# GPR_ADAPTER.net
KiCad netlist of a schematic drawn in EAGLE
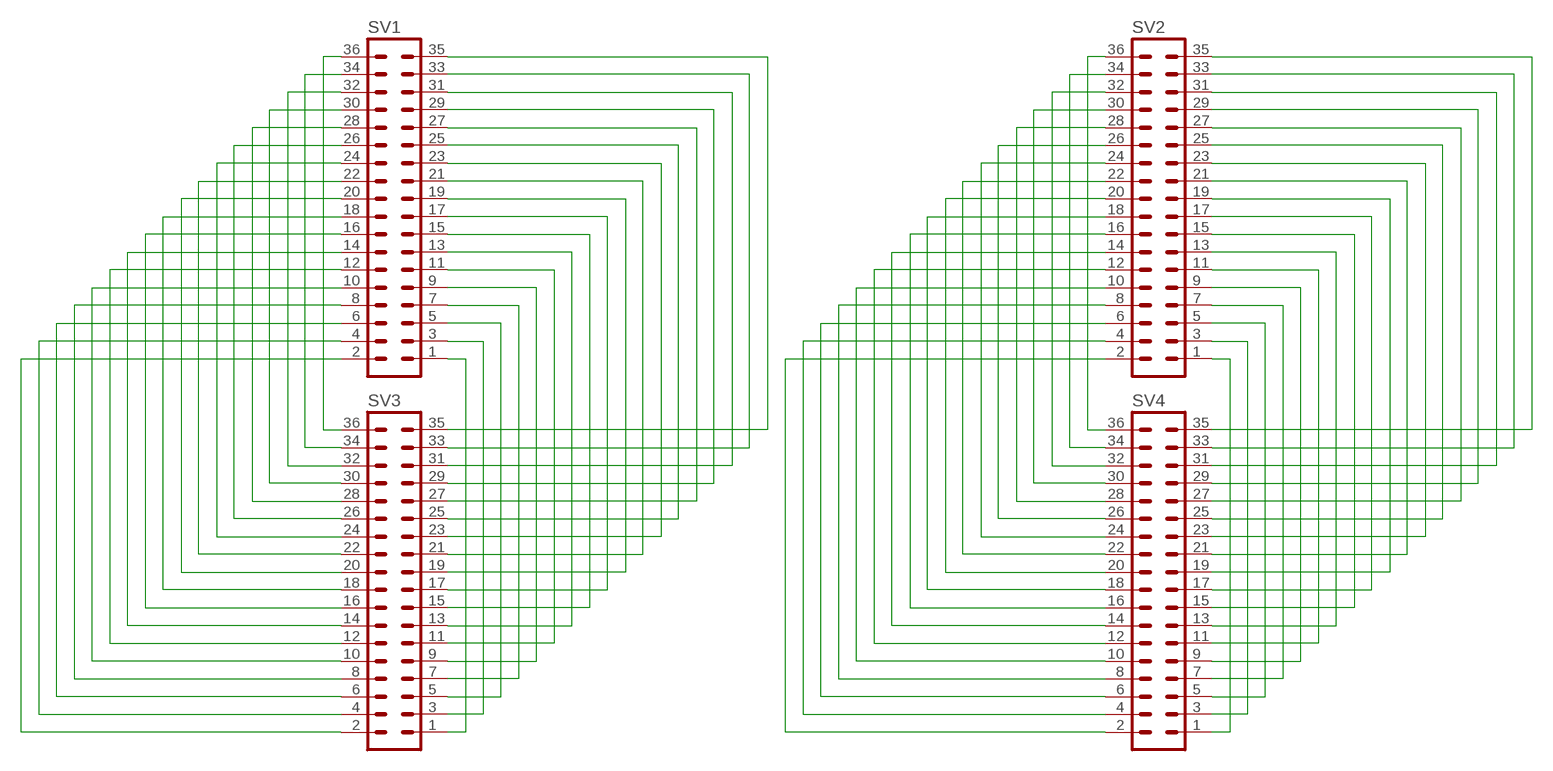
[diagram p0: schematic, sheet 1]

(export (version "E")
  (design (tool "Eeschema 10.0.6"))
  (components
    (comp (ref "SV1")
      (value "MA18-2")
      (footprint "eagle-import:MA18-2")
      (libsource (lib "eagle-import") (part "MA18-2"))
    )
    (comp (ref "SV2")
      (value "MA18-2")
      (footprint "eagle-import:MA18-2")
      (libsource (lib "eagle-import") (part "MA18-2"))
    )
    (comp (ref "SV3")
      (value "MA18-2")
      (footprint "eagle-import:MA18-2")
      (libsource (lib "eagle-import") (part "MA18-2"))
    )
    (comp (ref "SV4")
      (value "MA18-2")
      (footprint "eagle-import:MA18-2")
      (libsource (lib "eagle-import") (part "MA18-2"))
    )
  )
  (nets
    (net (code "1") (name "Net-(SV1-Pad1)") (class "Default")
      (node (ref "SV1") (pin "1") (pinfunction "1_1") (pintype "passive"))
      (node (ref "SV3") (pin "1") (pinfunction "1_1") (pintype "passive"))
    )
    (net (code "2") (name "Net-(SV1-Pad2)") (class "Default")
      (node (ref "SV1") (pin "2") (pinfunction "2_2") (pintype "passive"))
      (node (ref "SV3") (pin "2") (pinfunction "2_2") (pintype "passive"))
    )
    (net (code "3") (name "Net-(SV1-Pad3)") (class "Default")
      (node (ref "SV1") (pin "3") (pinfunction "3_3") (pintype "passive"))
      (node (ref "SV3") (pin "3") (pinfunction "3_3") (pintype "passive"))
    )
    (net (code "4") (name "Net-(SV1-Pad4)") (class "Default")
      (node (ref "SV1") (pin "4") (pinfunction "4_4") (pintype "passive"))
      (node (ref "SV3") (pin "4") (pinfunction "4_4") (pintype "passive"))
    )
    (net (code "5") (name "Net-(SV1-Pad5)") (class "Default")
      (node (ref "SV1") (pin "5") (pinfunction "5_5") (pintype "passive"))
      (node (ref "SV3") (pin "5") (pinfunction "5_5") (pintype "passive"))
    )
    (net (code "6") (name "Net-(SV1-Pad6)") (class "Default")
      (node (ref "SV1") (pin "6") (pinfunction "6_6") (pintype "passive"))
      (node (ref "SV3") (pin "6") (pinfunction "6_6") (pintype "passive"))
    )
    (net (code "7") (name "Net-(SV1-Pad7)") (class "Default")
      (node (ref "SV1") (pin "7") (pinfunction "7_7") (pintype "passive"))
      (node (ref "SV3") (pin "7") (pinfunction "7_7") (pintype "passive"))
    )
    (net (code "8") (name "Net-(SV1-Pad8)") (class "Default")
      (node (ref "SV1") (pin "8") (pinfunction "8_8") (pintype "passive"))
      (node (ref "SV3") (pin "8") (pinfunction "8_8") (pintype "passive"))
    )
    (net (code "9") (name "Net-(SV1-Pad9)") (class "Default")
      (node (ref "SV1") (pin "9") (pinfunction "9_9") (pintype "passive"))
      (node (ref "SV3") (pin "9") (pinfunction "9_9") (pintype "passive"))
    )
    (net (code "10") (name "Net-(SV1-Pad10)") (class "Default")
      (node (ref "SV1") (pin "10") (pinfunction "10_10") (pintype "passive"))
      (node (ref "SV3") (pin "10") (pinfunction "10_10") (pintype "passive"))
    )
    (net (code "11") (name "Net-(SV1-Pad11)") (class "Default")
      (node (ref "SV1") (pin "11") (pinfunction "11_11") (pintype "passive"))
      (node (ref "SV3") (pin "11") (pinfunction "11_11") (pintype "passive"))
    )
    (net (code "12") (name "Net-(SV1-Pad12)") (class "Default")
      (node (ref "SV1") (pin "12") (pinfunction "12_12") (pintype "passive"))
      (node (ref "SV3") (pin "12") (pinfunction "12_12") (pintype "passive"))
    )
    (net (code "13") (name "Net-(SV1-Pad13)") (class "Default")
      (node (ref "SV1") (pin "13") (pinfunction "13_13") (pintype "passive"))
      (node (ref "SV3") (pin "13") (pinfunction "13_13") (pintype "passive"))
    )
    (net (code "14") (name "Net-(SV1-Pad14)") (class "Default")
      (node (ref "SV1") (pin "14") (pinfunction "14_14") (pintype "passive"))
      (node (ref "SV3") (pin "14") (pinfunction "14_14") (pintype "passive"))
    )
    (net (code "15") (name "Net-(SV1-Pad15)") (class "Default")
      (node (ref "SV1") (pin "15") (pinfunction "15_15") (pintype "passive"))
      (node (ref "SV3") (pin "15") (pinfunction "15_15") (pintype "passive"))
    )
    (net (code "16") (name "Net-(SV1-Pad16)") (class "Default")
      (node (ref "SV1") (pin "16") (pinfunction "16_16") (pintype "passive"))
      (node (ref "SV3") (pin "16") (pinfunction "16_16") (pintype "passive"))
    )
    (net (code "17") (name "Net-(SV1-Pad17)") (class "Default")
      (node (ref "SV1") (pin "17") (pinfunction "17_17") (pintype "passive"))
      (node (ref "SV3") (pin "17") (pinfunction "17_17") (pintype "passive"))
    )
    (net (code "18") (name "Net-(SV1-Pad18)") (class "Default")
      (node (ref "SV1") (pin "18") (pinfunction "18_18") (pintype "passive"))
      (node (ref "SV3") (pin "18") (pinfunction "18_18") (pintype "passive"))
    )
    (net (code "19") (name "Net-(SV1-Pad19)") (class "Default")
      (node (ref "SV1") (pin "19") (pinfunction "19_19") (pintype "passive"))
      (node (ref "SV3") (pin "19") (pinfunction "19_19") (pintype "passive"))
    )
    (net (code "20") (name "Net-(SV1-Pad20)") (class "Default")
      (node (ref "SV1") (pin "20") (pinfunction "20_20") (pintype "passive"))
      (node (ref "SV3") (pin "20") (pinfunction "20_20") (pintype "passive"))
    )
    (net (code "21") (name "Net-(SV1-Pad21)") (class "Default")
      (node (ref "SV1") (pin "21") (pinfunction "21_21") (pintype "passive"))
      (node (ref "SV3") (pin "21") (pinfunction "21_21") (pintype "passive"))
    )
    (net (code "22") (name "Net-(SV1-Pad22)") (class "Default")
      (node (ref "SV1") (pin "22") (pinfunction "22_22") (pintype "passive"))
      (node (ref "SV3") (pin "22") (pinfunction "22_22") (pintype "passive"))
    )
    (net (code "23") (name "Net-(SV1-Pad23)") (class "Default")
      (node (ref "SV1") (pin "23") (pinfunction "23_23") (pintype "passive"))
      (node (ref "SV3") (pin "23") (pinfunction "23_23") (pintype "passive"))
    )
    (net (code "24") (name "Net-(SV1-Pad24)") (class "Default")
      (node (ref "SV1") (pin "24") (pinfunction "24_24") (pintype "passive"))
      (node (ref "SV3") (pin "24") (pinfunction "24_24") (pintype "passive"))
    )
    (net (code "25") (name "Net-(SV1-Pad25)") (class "Default")
      (node (ref "SV1") (pin "25") (pinfunction "25_25") (pintype "passive"))
      (node (ref "SV3") (pin "25") (pinfunction "25_25") (pintype "passive"))
    )
    (net (code "26") (name "Net-(SV1-Pad26)") (class "Default")
      (node (ref "SV1") (pin "26") (pinfunction "26_26") (pintype "passive"))
      (node (ref "SV3") (pin "26") (pinfunction "26_26") (pintype "passive"))
    )
    (net (code "27") (name "Net-(SV1-Pad27)") (class "Default")
      (node (ref "SV1") (pin "27") (pinfunction "27_27") (pintype "passive"))
      (node (ref "SV3") (pin "27") (pinfunction "27_27") (pintype "passive"))
    )
    (net (code "28") (name "Net-(SV1-Pad28)") (class "Default")
      (node (ref "SV1") (pin "28") (pinfunction "28_28") (pintype "passive"))
      (node (ref "SV3") (pin "28") (pinfunction "28_28") (pintype "passive"))
    )
    (net (code "29") (name "Net-(SV1-Pad29)") (class "Default")
      (node (ref "SV1") (pin "29") (pinfunction "29_29") (pintype "passive"))
      (node (ref "SV3") (pin "29") (pinfunction "29_29") (pintype "passive"))
    )
    (net (code "30") (name "Net-(SV1-Pad30)") (class "Default")
      (node (ref "SV1") (pin "30") (pinfunction "30_30") (pintype "passive"))
      (node (ref "SV3") (pin "30") (pinfunction "30_30") (pintype "passive"))
    )
    (net (code "31") (name "Net-(SV1-Pad31)") (class "Default")
      (node (ref "SV1") (pin "31") (pinfunction "31_31") (pintype "passive"))
      (node (ref "SV3") (pin "31") (pinfunction "31_31") (pintype "passive"))
    )
    (net (code "32") (name "Net-(SV1-Pad32)") (class "Default")
      (node (ref "SV1") (pin "32") (pinfunction "32_32") (pintype "passive"))
      (node (ref "SV3") (pin "32") (pinfunction "32_32") (pintype "passive"))
    )
    (net (code "33") (name "Net-(SV1-Pad33)") (class "Default")
      (node (ref "SV1") (pin "33") (pinfunction "33_33") (pintype "passive"))
      (node (ref "SV3") (pin "33") (pinfunction "33_33") (pintype "passive"))
    )
    (net (code "34") (name "Net-(SV1-Pad34)") (class "Default")
      (node (ref "SV1") (pin "34") (pinfunction "34_34") (pintype "passive"))
      (node (ref "SV3") (pin "34") (pinfunction "34_34") (pintype "passive"))
    )
    (net (code "35") (name "Net-(SV1-Pad35)") (class "Default")
      (node (ref "SV1") (pin "35") (pinfunction "35_35") (pintype "passive"))
      (node (ref "SV3") (pin "35") (pinfunction "35_35") (pintype "passive"))
    )
    (net (code "36") (name "Net-(SV1-Pad36)") (class "Default")
      (node (ref "SV1") (pin "36") (pinfunction "36_36") (pintype "passive"))
      (node (ref "SV3") (pin "36") (pinfunction "36_36") (pintype "passive"))
    )
    (net (code "37") (name "Net-(SV2-Pad1)") (class "Default")
      (node (ref "SV2") (pin "1") (pinfunction "1_1") (pintype "passive"))
      (node (ref "SV4") (pin "1") (pinfunction "1_1") (pintype "passive"))
    )
    (net (code "38") (name "Net-(SV2-Pad2)") (class "Default")
      (node (ref "SV2") (pin "2") (pinfunction "2_2") (pintype "passive"))
      (node (ref "SV4") (pin "2") (pinfunction "2_2") (pintype "passive"))
    )
    (net (code "39") (name "Net-(SV2-Pad3)") (class "Default")
      (node (ref "SV2") (pin "3") (pinfunction "3_3") (pintype "passive"))
      (node (ref "SV4") (pin "3") (pinfunction "3_3") (pintype "passive"))
    )
    (net (code "40") (name "Net-(SV2-Pad4)") (class "Default")
      (node (ref "SV2") (pin "4") (pinfunction "4_4") (pintype "passive"))
      (node (ref "SV4") (pin "4") (pinfunction "4_4") (pintype "passive"))
    )
    (net (code "41") (name "Net-(SV2-Pad5)") (class "Default")
      (node (ref "SV2") (pin "5") (pinfunction "5_5") (pintype "passive"))
      (node (ref "SV4") (pin "5") (pinfunction "5_5") (pintype "passive"))
    )
    (net (code "42") (name "Net-(SV2-Pad6)") (class "Default")
      (node (ref "SV2") (pin "6") (pinfunction "6_6") (pintype "passive"))
      (node (ref "SV4") (pin "6") (pinfunction "6_6") (pintype "passive"))
    )
    (net (code "43") (name "Net-(SV2-Pad7)") (class "Default")
      (node (ref "SV2") (pin "7") (pinfunction "7_7") (pintype "passive"))
      (node (ref "SV4") (pin "7") (pinfunction "7_7") (pintype "passive"))
    )
    (net (code "44") (name "Net-(SV2-Pad8)") (class "Default")
      (node (ref "SV2") (pin "8") (pinfunction "8_8") (pintype "passive"))
      (node (ref "SV4") (pin "8") (pinfunction "8_8") (pintype "passive"))
    )
    (net (code "45") (name "Net-(SV2-Pad9)") (class "Default")
      (node (ref "SV2") (pin "9") (pinfunction "9_9") (pintype "passive"))
      (node (ref "SV4") (pin "9") (pinfunction "9_9") (pintype "passive"))
    )
    (net (code "46") (name "Net-(SV2-Pad10)") (class "Default")
      (node (ref "SV2") (pin "10") (pinfunction "10_10") (pintype "passive"))
      (node (ref "SV4") (pin "10") (pinfunction "10_10") (pintype "passive"))
    )
    (net (code "47") (name "Net-(SV2-Pad11)") (class "Default")
      (node (ref "SV2") (pin "11") (pinfunction "11_11") (pintype "passive"))
      (node (ref "SV4") (pin "11") (pinfunction "11_11") (pintype "passive"))
    )
    (net (code "48") (name "Net-(SV2-Pad12)") (class "Default")
      (node (ref "SV2") (pin "12") (pinfunction "12_12") (pintype "passive"))
      (node (ref "SV4") (pin "12") (pinfunction "12_12") (pintype "passive"))
    )
    (net (code "49") (name "Net-(SV2-Pad13)") (class "Default")
      (node (ref "SV2") (pin "13") (pinfunction "13_13") (pintype "passive"))
      (node (ref "SV4") (pin "13") (pinfunction "13_13") (pintype "passive"))
    )
    (net (code "50") (name "Net-(SV2-Pad14)") (class "Default")
      (node (ref "SV2") (pin "14") (pinfunction "14_14") (pintype "passive"))
      (node (ref "SV4") (pin "14") (pinfunction "14_14") (pintype "passive"))
    )
    (net (code "51") (name "Net-(SV2-Pad15)") (class "Default")
      (node (ref "SV2") (pin "15") (pinfunction "15_15") (pintype "passive"))
      (node (ref "SV4") (pin "15") (pinfunction "15_15") (pintype "passive"))
    )
    (net (code "52") (name "Net-(SV2-Pad16)") (class "Default")
      (node (ref "SV2") (pin "16") (pinfunction "16_16") (pintype "passive"))
      (node (ref "SV4") (pin "16") (pinfunction "16_16") (pintype "passive"))
    )
    (net (code "53") (name "Net-(SV2-Pad17)") (class "Default")
      (node (ref "SV2") (pin "17") (pinfunction "17_17") (pintype "passive"))
      (node (ref "SV4") (pin "17") (pinfunction "17_17") (pintype "passive"))
    )
    (net (code "54") (name "Net-(SV2-Pad18)") (class "Default")
      (node (ref "SV2") (pin "18") (pinfunction "18_18") (pintype "passive"))
      (node (ref "SV4") (pin "18") (pinfunction "18_18") (pintype "passive"))
    )
    (net (code "55") (name "Net-(SV2-Pad19)") (class "Default")
      (node (ref "SV2") (pin "19") (pinfunction "19_19") (pintype "passive"))
      (node (ref "SV4") (pin "19") (pinfunction "19_19") (pintype "passive"))
    )
    (net (code "56") (name "Net-(SV2-Pad20)") (class "Default")
      (node (ref "SV2") (pin "20") (pinfunction "20_20") (pintype "passive"))
      (node (ref "SV4") (pin "20") (pinfunction "20_20") (pintype "passive"))
    )
    (net (code "57") (name "Net-(SV2-Pad21)") (class "Default")
      (node (ref "SV2") (pin "21") (pinfunction "21_21") (pintype "passive"))
      (node (ref "SV4") (pin "21") (pinfunction "21_21") (pintype "passive"))
    )
    (net (code "58") (name "Net-(SV2-Pad22)") (class "Default")
      (node (ref "SV2") (pin "22") (pinfunction "22_22") (pintype "passive"))
      (node (ref "SV4") (pin "22") (pinfunction "22_22") (pintype "passive"))
    )
    (net (code "59") (name "Net-(SV2-Pad23)") (class "Default")
      (node (ref "SV2") (pin "23") (pinfunction "23_23") (pintype "passive"))
      (node (ref "SV4") (pin "23") (pinfunction "23_23") (pintype "passive"))
    )
    (net (code "60") (name "Net-(SV2-Pad24)") (class "Default")
      (node (ref "SV2") (pin "24") (pinfunction "24_24") (pintype "passive"))
      (node (ref "SV4") (pin "24") (pinfunction "24_24") (pintype "passive"))
    )
    (net (code "61") (name "Net-(SV2-Pad25)") (class "Default")
      (node (ref "SV2") (pin "25") (pinfunction "25_25") (pintype "passive"))
      (node (ref "SV4") (pin "25") (pinfunction "25_25") (pintype "passive"))
    )
    (net (code "62") (name "Net-(SV2-Pad26)") (class "Default")
      (node (ref "SV2") (pin "26") (pinfunction "26_26") (pintype "passive"))
      (node (ref "SV4") (pin "26") (pinfunction "26_26") (pintype "passive"))
    )
    (net (code "63") (name "Net-(SV2-Pad27)") (class "Default")
      (node (ref "SV2") (pin "27") (pinfunction "27_27") (pintype "passive"))
      (node (ref "SV4") (pin "27") (pinfunction "27_27") (pintype "passive"))
    )
    (net (code "64") (name "Net-(SV2-Pad28)") (class "Default")
      (node (ref "SV2") (pin "28") (pinfunction "28_28") (pintype "passive"))
      (node (ref "SV4") (pin "28") (pinfunction "28_28") (pintype "passive"))
    )
    (net (code "65") (name "Net-(SV2-Pad29)") (class "Default")
      (node (ref "SV2") (pin "29") (pinfunction "29_29") (pintype "passive"))
      (node (ref "SV4") (pin "29") (pinfunction "29_29") (pintype "passive"))
    )
    (net (code "66") (name "Net-(SV2-Pad30)") (class "Default")
      (node (ref "SV2") (pin "30") (pinfunction "30_30") (pintype "passive"))
      (node (ref "SV4") (pin "30") (pinfunction "30_30") (pintype "passive"))
    )
    (net (code "67") (name "Net-(SV2-Pad31)") (class "Default")
      (node (ref "SV2") (pin "31") (pinfunction "31_31") (pintype "passive"))
      (node (ref "SV4") (pin "31") (pinfunction "31_31") (pintype "passive"))
    )
    (net (code "68") (name "Net-(SV2-Pad32)") (class "Default")
      (node (ref "SV2") (pin "32") (pinfunction "32_32") (pintype "passive"))
      (node (ref "SV4") (pin "32") (pinfunction "32_32") (pintype "passive"))
    )
    (net (code "69") (name "Net-(SV2-Pad33)") (class "Default")
      (node (ref "SV2") (pin "33") (pinfunction "33_33") (pintype "passive"))
      (node (ref "SV4") (pin "33") (pinfunction "33_33") (pintype "passive"))
    )
    (net (code "70") (name "Net-(SV2-Pad34)") (class "Default")
      (node (ref "SV2") (pin "34") (pinfunction "34_34") (pintype "passive"))
      (node (ref "SV4") (pin "34") (pinfunction "34_34") (pintype "passive"))
    )
    (net (code "71") (name "Net-(SV2-Pad35)") (class "Default")
      (node (ref "SV2") (pin "35") (pinfunction "35_35") (pintype "passive"))
      (node (ref "SV4") (pin "35") (pinfunction "35_35") (pintype "passive"))
    )
    (net (code "72") (name "Net-(SV2-Pad36)") (class "Default")
      (node (ref "SV2") (pin "36") (pinfunction "36_36") (pintype "passive"))
      (node (ref "SV4") (pin "36") (pinfunction "36_36") (pintype "passive"))
    )
  )
)
